# 05_LMS1_Misc.net
KiCad netlist of a schematic drawn in Altium Designer
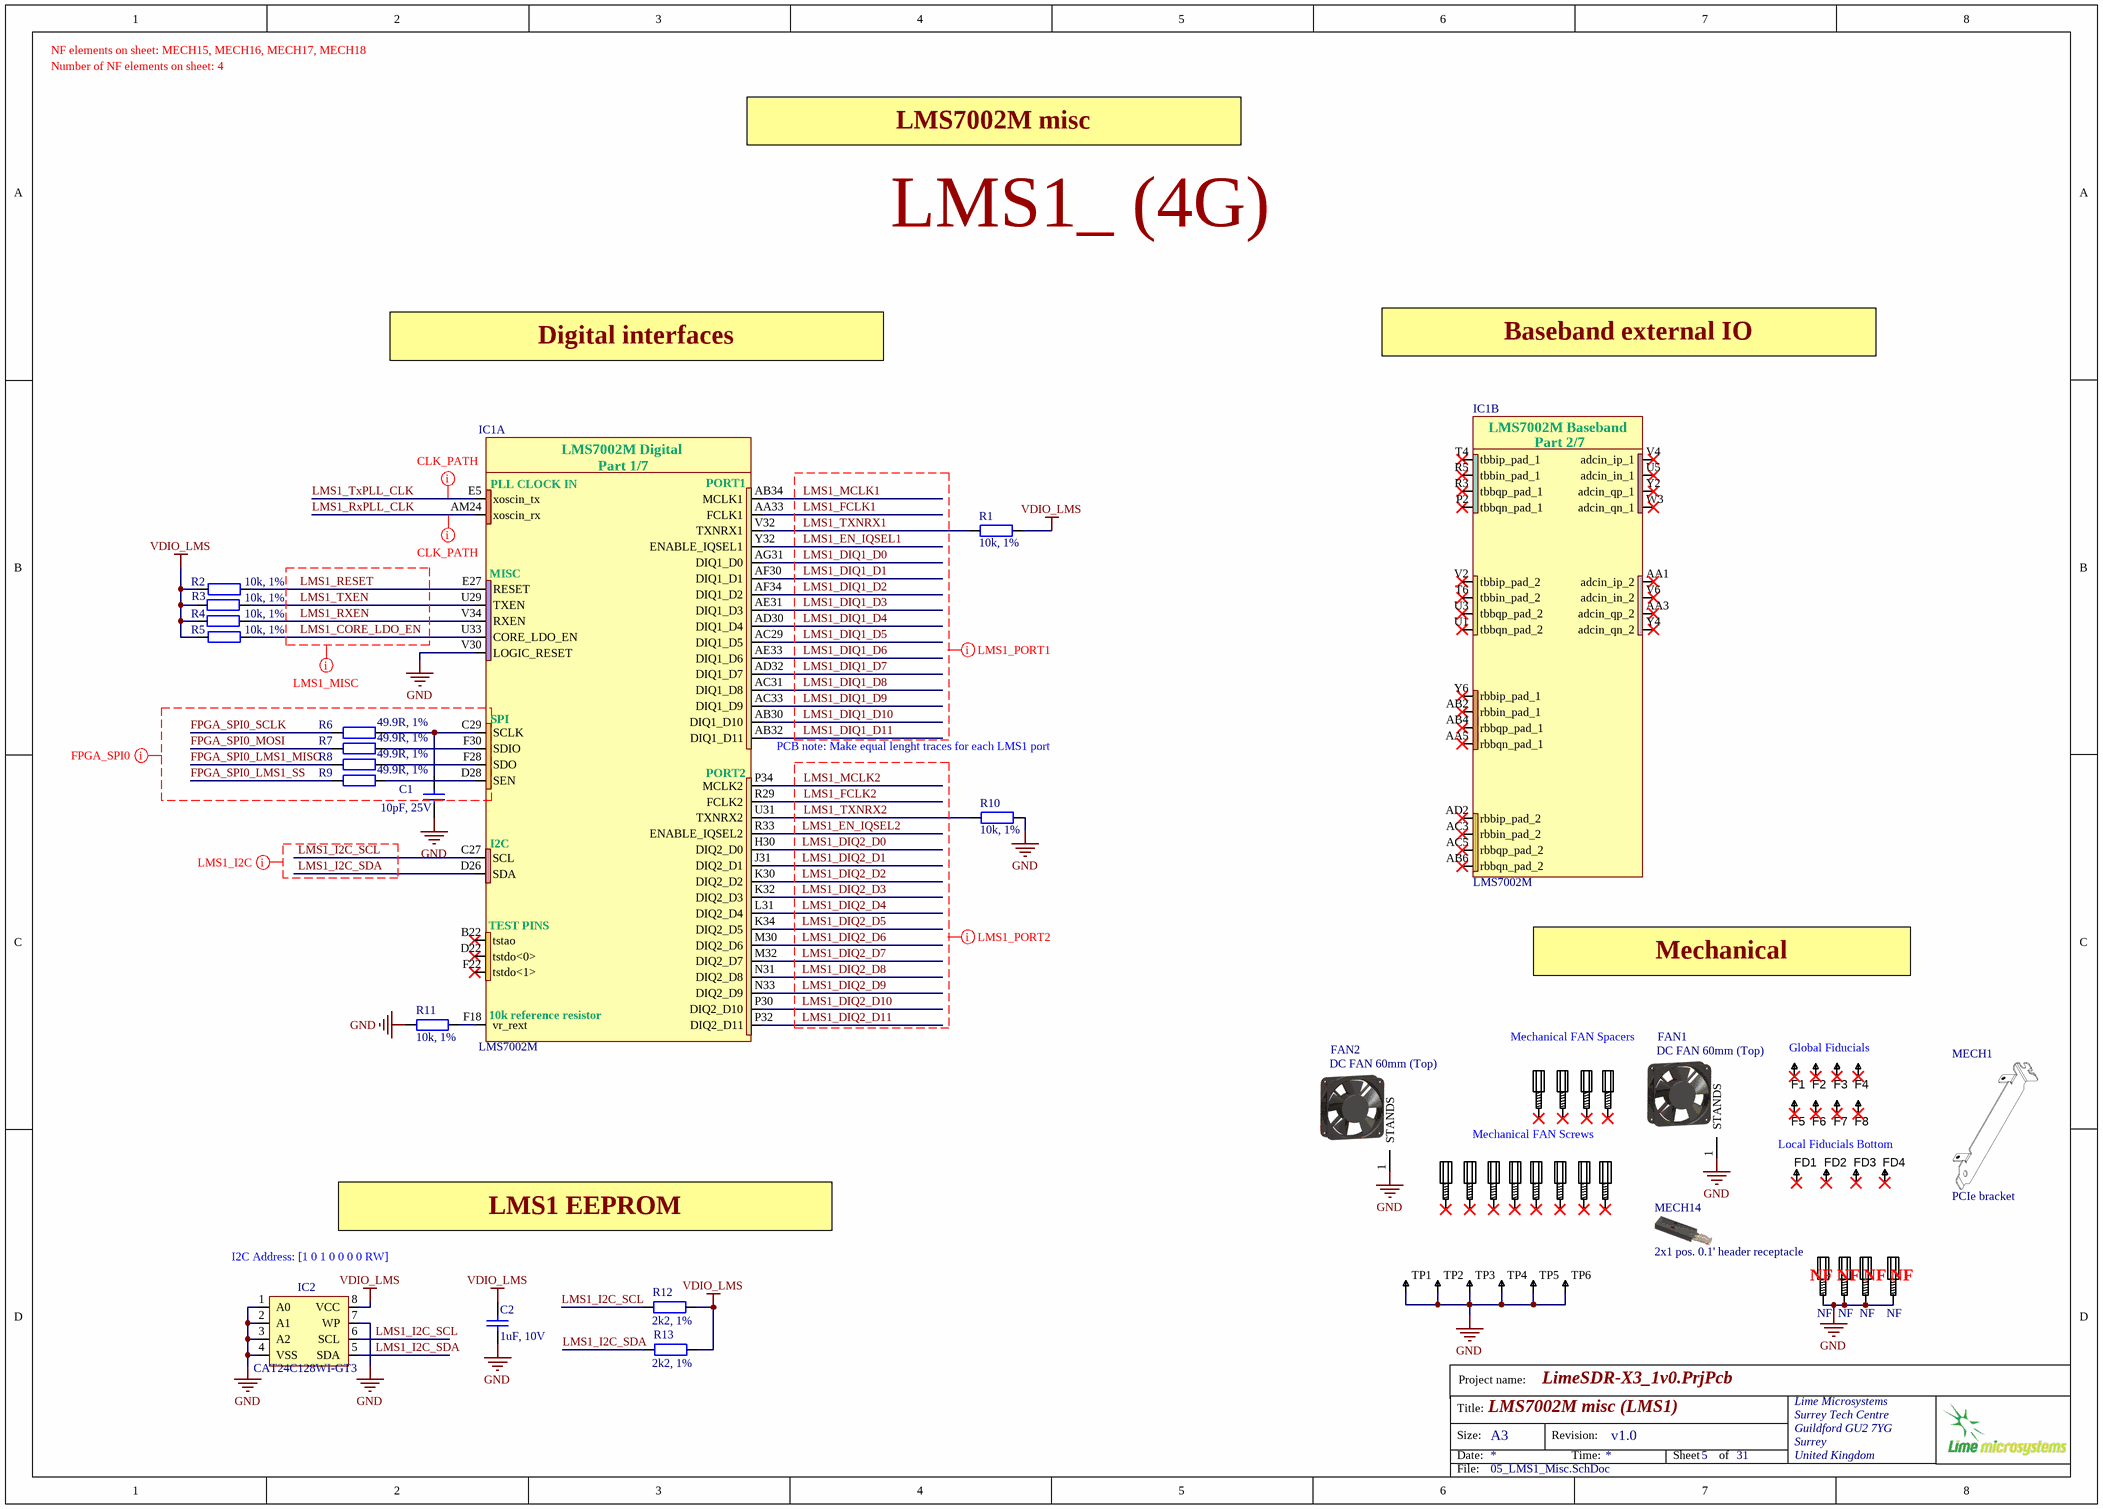
[diagram p0: 05_LMS1_Misc.SchDoc]

(export (version "E")
  (design (tool "Eeschema 10.0.6"))
  (components
    (comp (ref "C1")
      (value "10pF, 25V")
      (footprint "CAP0402")
      (fields (field (name "MANUFACTURER") "AVX"))
      (libsource (lib "") (part "Cap_0402_1"))
    )
    (comp (ref "C2")
      (value "1uF, 10V")
      (footprint "CAP0402")
      (fields (field (name "MANUFACTURER") "TDK"))
      (libsource (lib "LimeMicroAltiumLib_schLib") (part "Cap_0402"))
    )
    (comp (ref "F1")
      (value "Fiducial")
      (footprint "Fiducial")
      (libsource (lib "VGTU_Altium_lib") (part "Fiducial"))
    )
    (comp (ref "F2")
      (value "Fiducial")
      (footprint "Fiducial")
      (libsource (lib "VGTU_Altium_lib") (part "Fiducial"))
    )
    (comp (ref "F3")
      (value "Fiducial")
      (footprint "Fiducial")
      (libsource (lib "VGTU_Altium_lib") (part "Fiducial"))
    )
    (comp (ref "F4")
      (value "Fiducial")
      (footprint "Fiducial")
      (libsource (lib "VGTU_Altium_lib") (part "Fiducial"))
    )
    (comp (ref "F5")
      (value "Fiducial")
      (footprint "Fiducial")
      (libsource (lib "VGTU_Altium_lib") (part "Fiducial"))
    )
    (comp (ref "F6")
      (value "Fiducial")
      (footprint "Fiducial")
      (libsource (lib "VGTU_Altium_lib") (part "Fiducial"))
    )
    (comp (ref "F7")
      (value "Fiducial")
      (footprint "Fiducial")
      (libsource (lib "VGTU_Altium_lib") (part "Fiducial"))
    )
    (comp (ref "F8")
      (value "Fiducial")
      (footprint "Fiducial")
      (libsource (lib "VGTU_Altium_lib") (part "Fiducial"))
    )
    (comp (ref "FAN1")
      (value "DC FAN 60mm (Top)")
      (footprint "FAN_60mm")
      (fields (field (name "MANUFACTURER") "Sunon"))
      (libsource (lib "LimeMicroAltiumLib_schLib") (part "12V_DC_FAN"))
    )
    (comp (ref "FAN2")
      (value "DC FAN 60mm (Top)")
      (footprint "FAN_60mm")
      (fields (field (name "MANUFACTURER") "Sunon"))
      (libsource (lib "LimeMicroAltiumLib_schLib") (part "12V_DC_FAN"))
    )
    (comp (ref "FD1")
      (value "Fiducial")
      (footprint "Fiducial_local")
      (libsource (lib "LimeMicroAltiumLib_schLib") (part "Fiducial"))
    )
    (comp (ref "FD2")
      (value "Fiducial")
      (footprint "Fiducial_local")
      (libsource (lib "") (part "Fiducial_1"))
    )
    (comp (ref "FD3")
      (value "Fiducial")
      (footprint "Fiducial_local")
      (libsource (lib "") (part "Fiducial_2"))
    )
    (comp (ref "FD4")
      (value "Fiducial")
      (footprint "Fiducial_local")
      (libsource (lib "") (part "Fiducial_1"))
    )
    (comp (ref "IC1")
      (value "LMS7002M")
      (footprint "LMS7002M_v5")
      (description "Schematic symbol revision 4. Default footprint - 0.31mm pad")
      (fields (field (name "MANUFACTURER") "Lime Microsystems"))
      (libsource (lib "LimeMicroAltiumLib_schLib_r04") (part "LMS7002Mr4"))
    )
    (comp (ref "IC2")
      (value "CAT24C128WI-GT3")
      (footprint "SOIC127P600-8DL_v2")
      (fields (field (name "MANUFACTURER") "ON Semiconductor") (field (name "BASE PART NUMBER") "CAT24C128"))
      (libsource (lib "LimeMicroAltiumLib_schLib") (part "24FC64F"))
    )
    (comp (ref "MECH1")
      (value "PCIe bracket")
      (footprint "PCIe_bracket")
      (fields (field (name "MANUFACTURER") "Keystone Electronics"))
      (libsource (lib "LimeMicroAltiumLib_schLib_r01") (part "PCIe_bracket"))
    )
    (comp (ref "MECH2")
      (value "Spacer M3")
      (description "STANDOFF M/F MET 5MM HEX 10MM L")
      (fields (field (name "MANUFACTURER") "BOSSARD"))
      (libsource (lib "LimeMicroAltiumLib_schLib") (part "STANDOFF_M-F_THREADED_M3x8x10mm_HEX_5mm dia"))
    )
    (comp (ref "MECH3")
      (value "Spacer M3")
      (description "STANDOFF M/F MET 5MM HEX 10MM L")
      (fields (field (name "MANUFACTURER") "BOSSARD"))
      (libsource (lib "LimeMicroAltiumLib_schLib") (part "STANDOFF_M-F_THREADED_M3x8x10mm_HEX_5mm dia"))
    )
    (comp (ref "MECH4")
      (value "Spacer M3")
      (description "STANDOFF M/F MET 5MM HEX 10MM L")
      (fields (field (name "MANUFACTURER") "BOSSARD"))
      (libsource (lib "LimeMicroAltiumLib_schLib") (part "STANDOFF_M-F_THREADED_M3x8x10mm_HEX_5mm dia"))
    )
    (comp (ref "MECH5")
      (value "Spacer M3")
      (description "STANDOFF M/F MET 5MM HEX 10MM L")
      (fields (field (name "MANUFACTURER") "BOSSARD"))
      (libsource (lib "LimeMicroAltiumLib_schLib") (part "STANDOFF_M-F_THREADED_M3x8x10mm_HEX_5mm dia"))
    )
    (comp (ref "MECH6")
      (value "Screws M3")
      (description "STANDOFF M/F MET 5MM HEX 10MM L")
      (fields (field (name "MANUFACTURER") "BOSSARD"))
      (libsource (lib "") (part "STANDOFF_M-F_THREADED_M3x8x10mm_HEX_5mm dia_1"))
    )
    (comp (ref "MECH7")
      (value "Screws M3")
      (description "STANDOFF M/F MET 5MM HEX 10MM L")
      (fields (field (name "MANUFACTURER") "BOSSARD"))
      (libsource (lib "") (part "STANDOFF_M-F_THREADED_M3x8x10mm_HEX_5mm dia_1"))
    )
    (comp (ref "MECH8")
      (value "Screws M3")
      (description "STANDOFF M/F MET 5MM HEX 10MM L")
      (fields (field (name "MANUFACTURER") "BOSSARD"))
      (libsource (lib "") (part "STANDOFF_M-F_THREADED_M3x8x10mm_HEX_5mm dia_1"))
    )
    (comp (ref "MECH9")
      (value "Screws M3")
      (description "STANDOFF M/F MET 5MM HEX 10MM L")
      (fields (field (name "MANUFACTURER") "BOSSARD"))
      (libsource (lib "") (part "STANDOFF_M-F_THREADED_M3x8x10mm_HEX_5mm dia_1"))
    )
    (comp (ref "MECH10")
      (value "Screws M3")
      (description "STANDOFF M/F MET 5MM HEX 10MM L")
      (fields (field (name "MANUFACTURER") "BOSSARD"))
      (libsource (lib "") (part "STANDOFF_M-F_THREADED_M3x8x10mm_HEX_5mm dia_1"))
    )
    (comp (ref "MECH11")
      (value "Screws M3")
      (description "STANDOFF M/F MET 5MM HEX 10MM L")
      (fields (field (name "MANUFACTURER") "BOSSARD"))
      (libsource (lib "") (part "STANDOFF_M-F_THREADED_M3x8x10mm_HEX_5mm dia_1"))
    )
    (comp (ref "MECH12")
      (value "Screws M3")
      (description "STANDOFF M/F MET 5MM HEX 10MM L")
      (fields (field (name "MANUFACTURER") "BOSSARD"))
      (libsource (lib "") (part "STANDOFF_M-F_THREADED_M3x8x10mm_HEX_5mm dia_1"))
    )
    (comp (ref "MECH13")
      (value "Screws M3")
      (description "STANDOFF M/F MET 5MM HEX 10MM L")
      (fields (field (name "MANUFACTURER") "BOSSARD"))
      (libsource (lib "") (part "STANDOFF_M-F_THREADED_M3x8x10mm_HEX_5mm dia_1"))
    )
    (comp (ref "MECH14")
      (value "2x1 pos. 0.1' header receptacle")
      (fields (field (name "MANUFACTURER") "Molex"))
      (libsource (lib "LimeMicroAltiumLib_schLib_r01") (part "Header_1x2_receptacle"))
    )
    (comp (ref "MECH15")
      (value "Standoff")
      (footprint "PCB_standoff")
      (description "STANDOFF M/F MET 5MM HEX 10MM L")
      (fields (field (name "MANUFACTURER") "FIX&FASTEN") (field (name "ASSEMBLY INFO") "NF"))
      (libsource (lib "") (part "STANDOFF_M-F_THREADED_M3x8x10mm_HEX_5mm dia_1"))
    )
    (comp (ref "MECH16")
      (value "Standoff")
      (footprint "PCB_standoff")
      (description "STANDOFF M/F MET 5MM HEX 10MM L")
      (fields (field (name "MANUFACTURER") "FIX&FASTEN") (field (name "ASSEMBLY INFO") "NF"))
      (libsource (lib "") (part "STANDOFF_M-F_THREADED_M3x8x10mm_HEX_5mm dia_1"))
    )
    (comp (ref "MECH17")
      (value "Standoff")
      (footprint "PCB_standoff")
      (description "STANDOFF M/F MET 5MM HEX 10MM L")
      (fields (field (name "MANUFACTURER") "FIX&FASTEN") (field (name "ASSEMBLY INFO") "NF"))
      (libsource (lib "") (part "STANDOFF_M-F_THREADED_M3x8x10mm_HEX_5mm dia_1"))
    )
    (comp (ref "MECH18")
      (value "Standoff")
      (footprint "PCB_standoff")
      (description "STANDOFF M/F MET 5MM HEX 10MM L")
      (fields (field (name "MANUFACTURER") "FIX&FASTEN") (field (name "ASSEMBLY INFO") "NF"))
      (libsource (lib "") (part "STANDOFF_M-F_THREADED_M3x8x10mm_HEX_5mm dia_2"))
    )
    (comp (ref "R1")
      (value "10k, 1%")
      (footprint "RES0402")
      (fields (field (name "MANUFACTURER") "Yageo") (field (name "TOLERANCE") "±1%"))
      (libsource (lib "LimeMicroAltiumLib_schLib") (part "Res_0402"))
    )
    (comp (ref "R2")
      (value "10k, 1%")
      (footprint "RES0402")
      (fields (field (name "MANUFACTURER") "Yageo") (field (name "TOLERANCE") "±1%"))
      (libsource (lib "LimeMicroAltiumLib_schLib") (part "Res_0402"))
    )
    (comp (ref "R3")
      (value "10k, 1%")
      (footprint "RES0402")
      (fields (field (name "MANUFACTURER") "Yageo") (field (name "TOLERANCE") "±1%"))
      (libsource (lib "LimeMicroAltiumLib_schLib") (part "Res_0402"))
    )
    (comp (ref "R4")
      (value "10k, 1%")
      (footprint "RES0402")
      (fields (field (name "MANUFACTURER") "Yageo") (field (name "TOLERANCE") "±1%"))
      (libsource (lib "LimeMicroAltiumLib_schLib") (part "Res_0402"))
    )
    (comp (ref "R5")
      (value "10k, 1%")
      (footprint "RES0402")
      (fields (field (name "MANUFACTURER") "Yageo") (field (name "TOLERANCE") "±1%"))
      (libsource (lib "LimeMicroAltiumLib_schLib") (part "Res_0402"))
    )
    (comp (ref "R6")
      (value "49.9R, 1%")
      (footprint "RES0402")
      (fields
        (field (name "TOLERANCE") "±1%")
        (field (name "MANUFACTURER") "Samsung Electro-Mechanics America, Inc.")
        (field (name "MANUFACTURER PART NUMBER") "RC1005F49R9CS")
      )
      (libsource (lib "LimeMicroAltiumLib_schLib") (part "Res_0402"))
    )
    (comp (ref "R7")
      (value "49.9R, 1%")
      (footprint "RES0402")
      (fields
        (field (name "TOLERANCE") "±1%")
        (field (name "MANUFACTURER") "Samsung Electro-Mechanics America, Inc.")
        (field (name "MANUFACTURER PART NUMBER") "RC1005F49R9CS")
      )
      (libsource (lib "LimeMicroAltiumLib_schLib") (part "Res_0402"))
    )
    (comp (ref "R8")
      (value "49.9R, 1%")
      (footprint "RES0402")
      (fields
        (field (name "TOLERANCE") "±1%")
        (field (name "MANUFACTURER") "Samsung Electro-Mechanics America, Inc.")
        (field (name "MANUFACTURER PART NUMBER") "RC1005F49R9CS")
      )
      (libsource (lib "LimeMicroAltiumLib_schLib") (part "Res_0402"))
    )
    (comp (ref "R9")
      (value "49.9R, 1%")
      (footprint "RES0402")
      (fields
        (field (name "TOLERANCE") "±1%")
        (field (name "MANUFACTURER") "Samsung Electro-Mechanics America, Inc.")
        (field (name "MANUFACTURER PART NUMBER") "RC1005F49R9CS")
      )
      (libsource (lib "LimeMicroAltiumLib_schLib") (part "Res_0402"))
    )
    (comp (ref "R10")
      (value "10k, 1%")
      (footprint "RES0402")
      (fields (field (name "MANUFACTURER") "Yageo") (field (name "TOLERANCE") "±1%"))
      (libsource (lib "LimeMicroAltiumLib_schLib") (part "Res_0402"))
    )
    (comp (ref "R11")
      (value "10k, 1%")
      (footprint "RES0402")
      (fields (field (name "MANUFACTURER") "Yageo") (field (name "TOLERANCE") "±1%"))
      (libsource (lib "") (part "Res_0402_1"))
    )
    (comp (ref "R12")
      (value "2k2, 1%")
      (footprint "RES0402")
      (fields (field (name "MANUFACTURER") "Stackpole Electronics Inc") (field (name "TOLERANCE") "±1%"))
      (libsource (lib "LimeMicroAltiumLib_schLib") (part "Res_0402"))
    )
    (comp (ref "R13")
      (value "2k2, 1%")
      (footprint "RES0402")
      (fields (field (name "MANUFACTURER") "Stackpole Electronics Inc") (field (name "TOLERANCE") "±1%"))
      (libsource (lib "LimeMicroAltiumLib_schLib") (part "Res_0402"))
    )
    (comp (ref "TP1")
      (value "TESTPOINT_THT_MINI")
      (footprint "TP-SMD-LOW_PROFILE")
      (description "Test Point PCB mount Miniature White")
      (fields (field (name "MANUFACTURER") "Harwin Inc"))
      (libsource (lib "LimeMicroAltiumLib_schLib") (part "TESTPOINT_THT_MINI"))
    )
    (comp (ref "TP2")
      (value "TESTPOINT_THT_MINI")
      (footprint "TP-SMD-LOW_PROFILE")
      (description "Test Point PCB mount Miniature White")
      (fields (field (name "MANUFACTURER") "Harwin Inc"))
      (libsource (lib "LimeMicroAltiumLib_schLib") (part "TESTPOINT_THT_MINI"))
    )
    (comp (ref "TP3")
      (value "TESTPOINT_THT_MINI")
      (footprint "TP-SMD-LOW_PROFILE")
      (description "Test Point PCB mount Miniature White")
      (fields (field (name "MANUFACTURER") "Harwin Inc"))
      (libsource (lib "LimeMicroAltiumLib_schLib") (part "TESTPOINT_THT_MINI"))
    )
    (comp (ref "TP4")
      (value "TESTPOINT_THT_MINI")
      (footprint "TP-SMD-LOW_PROFILE")
      (description "Test Point PCB mount Miniature White")
      (fields (field (name "MANUFACTURER") "Harwin Inc"))
      (libsource (lib "LimeMicroAltiumLib_schLib") (part "TESTPOINT_THT_MINI"))
    )
    (comp (ref "TP5")
      (value "TESTPOINT_THT_MINI")
      (footprint "TP-SMD-LOW_PROFILE")
      (description "Test Point PCB mount Miniature White")
      (fields (field (name "MANUFACTURER") "Harwin Inc"))
      (libsource (lib "LimeMicroAltiumLib_schLib") (part "TESTPOINT_THT_MINI"))
    )
    (comp (ref "TP6")
      (value "TESTPOINT_THT_MINI")
      (footprint "TP-SMD-LOW_PROFILE")
      (description "Test Point PCB mount Miniature White")
      (fields (field (name "MANUFACTURER") "Harwin Inc"))
      (libsource (lib "LimeMicroAltiumLib_schLib") (part "TESTPOINT_THT_MINI"))
    )
  )
  (nets
    (net (code "1") (name "/FPGA_SPI0_LMS1_MISO") (class "Default")
      (node (ref "R8") (pin "2") (pinfunction "2_2") (pintype "passive"))
    )
    (net (code "2") (name "/FPGA_SPI0_LMS1_SS") (class "Default")
      (node (ref "R9") (pin "2") (pinfunction "2_2") (pintype "passive"))
    )
    (net (code "3") (name "/FPGA_SPI0_MOSI") (class "Default")
      (node (ref "R7") (pin "2") (pinfunction "2_2") (pintype "passive"))
    )
    (net (code "4") (name "/FPGA_SPI0_SCLK") (class "Default")
      (node (ref "R6") (pin "2") (pinfunction "2_2") (pintype "passive"))
    )
    (net (code "5") (name "/LMS1_CORE_LDO_EN") (class "Default")
      (node (ref "IC1") (pin "U33") (pinfunction "CORE_LDO_EN_U33") (pintype "passive"))
      (node (ref "R5") (pin "1") (pinfunction "1_1") (pintype "passive"))
    )
    (net (code "6") (name "/LMS1_DIQ1_D0") (class "Default")
      (node (ref "IC1") (pin "AG31") (pinfunction "DIQ1_D0_AG31") (pintype "passive"))
    )
    (net (code "7") (name "/LMS1_DIQ1_D1") (class "Default")
      (node (ref "IC1") (pin "AF30") (pinfunction "DIQ1_D1_AF30") (pintype "passive"))
    )
    (net (code "8") (name "/LMS1_DIQ1_D2") (class "Default")
      (node (ref "IC1") (pin "AF34") (pinfunction "DIQ1_D2_AF34") (pintype "passive"))
    )
    (net (code "9") (name "/LMS1_DIQ1_D3") (class "Default")
      (node (ref "IC1") (pin "AE31") (pinfunction "DIQ1_D3_AE31") (pintype "passive"))
    )
    (net (code "10") (name "/LMS1_DIQ1_D4") (class "Default")
      (node (ref "IC1") (pin "AD30") (pinfunction "DIQ1_D4_AD30") (pintype "passive"))
    )
    (net (code "11") (name "/LMS1_DIQ1_D5") (class "Default")
      (node (ref "IC1") (pin "AC29") (pinfunction "DIQ1_D5_AC29") (pintype "passive"))
    )
    (net (code "12") (name "/LMS1_DIQ1_D6") (class "Default")
      (node (ref "IC1") (pin "AE33") (pinfunction "DIQ1_D6_AE33") (pintype "passive"))
    )
    (net (code "13") (name "/LMS1_DIQ1_D7") (class "Default")
      (node (ref "IC1") (pin "AD32") (pinfunction "DIQ1_D7_AD32") (pintype "passive"))
    )
    (net (code "14") (name "/LMS1_DIQ1_D8") (class "Default")
      (node (ref "IC1") (pin "AC31") (pinfunction "DIQ1_D8_AC31") (pintype "passive"))
    )
    (net (code "15") (name "/LMS1_DIQ1_D9") (class "Default")
      (node (ref "IC1") (pin "AC33") (pinfunction "DIQ1_D9_AC33") (pintype "passive"))
    )
    (net (code "16") (name "/LMS1_DIQ1_D10") (class "Default")
      (node (ref "IC1") (pin "AB30") (pinfunction "DIQ1_D10_AB30") (pintype "passive"))
    )
    (net (code "17") (name "/LMS1_DIQ1_D11") (class "Default")
      (node (ref "IC1") (pin "AB32") (pinfunction "DIQ1_D11_AB32") (pintype "passive"))
    )
    (net (code "18") (name "/LMS1_DIQ2_D0") (class "Default")
      (node (ref "IC1") (pin "H30") (pinfunction "DIQ2_D0_H30") (pintype "passive"))
    )
    (net (code "19") (name "/LMS1_DIQ2_D1") (class "Default")
      (node (ref "IC1") (pin "J31") (pinfunction "DIQ2_D1_J31") (pintype "passive"))
    )
    (net (code "20") (name "/LMS1_DIQ2_D2") (class "Default")
      (node (ref "IC1") (pin "K30") (pinfunction "DIQ2_D2_K30") (pintype "passive"))
    )
    (net (code "21") (name "/LMS1_DIQ2_D3") (class "Default")
      (node (ref "IC1") (pin "K32") (pinfunction "DIQ2_D3_K32") (pintype "passive"))
    )
    (net (code "22") (name "/LMS1_DIQ2_D4") (class "Default")
      (node (ref "IC1") (pin "L31") (pinfunction "DIQ2_D4_L31") (pintype "passive"))
    )
    (net (code "23") (name "/LMS1_DIQ2_D5") (class "Default")
      (node (ref "IC1") (pin "K34") (pinfunction "DIQ2_D5_K34") (pintype "passive"))
    )
    (net (code "24") (name "/LMS1_DIQ2_D6") (class "Default")
      (node (ref "IC1") (pin "M30") (pinfunction "DIQ2_D6_M30") (pintype "passive"))
    )
    (net (code "25") (name "/LMS1_DIQ2_D7") (class "Default")
      (node (ref "IC1") (pin "M32") (pinfunction "DIQ2_D7_M32") (pintype "passive"))
    )
    (net (code "26") (name "/LMS1_DIQ2_D8") (class "Default")
      (node (ref "IC1") (pin "N31") (pinfunction "DIQ2_D8_N31") (pintype "passive"))
    )
    (net (code "27") (name "/LMS1_DIQ2_D9") (class "Default")
      (node (ref "IC1") (pin "N33") (pinfunction "DIQ2_D9_N33") (pintype "passive"))
    )
    (net (code "28") (name "/LMS1_DIQ2_D10") (class "Default")
      (node (ref "IC1") (pin "P30") (pinfunction "DIQ2_D10_P30") (pintype "passive"))
    )
    (net (code "29") (name "/LMS1_DIQ2_D11") (class "Default")
      (node (ref "IC1") (pin "P32") (pinfunction "DIQ2_D11_P32") (pintype "passive"))
    )
    (net (code "30") (name "/LMS1_EN_IQSEL1") (class "Default")
      (node (ref "IC1") (pin "Y32") (pinfunction "ENABLE_IQSEL1_Y32") (pintype "passive"))
    )
    (net (code "31") (name "/LMS1_EN_IQSEL2") (class "Default")
      (node (ref "IC1") (pin "R33") (pinfunction "ENABLE_IQSEL2_R33") (pintype "passive"))
    )
    (net (code "32") (name "/LMS1_FCLK1") (class "Default")
      (node (ref "IC1") (pin "AA33") (pinfunction "FCLK1_AA33") (pintype "passive"))
    )
    (net (code "33") (name "/LMS1_FCLK2") (class "Default")
      (node (ref "IC1") (pin "R29") (pinfunction "FCLK2_R29") (pintype "passive"))
    )
    (net (code "34") (name "/LMS1_I2C_SCL") (class "Default")
      (node (ref "IC1") (pin "C27") (pinfunction "SCL_C27") (pintype "passive"))
      (node (ref "IC2") (pin "6") (pinfunction "SCL_6") (pintype "passive"))
      (node (ref "R12") (pin "2") (pinfunction "2_2") (pintype "passive"))
    )
    (net (code "35") (name "/LMS1_I2C_SDA") (class "Default")
      (node (ref "IC1") (pin "D26") (pinfunction "SDA_D26") (pintype "passive"))
      (node (ref "IC2") (pin "5") (pinfunction "SDA_5") (pintype "passive"))
      (node (ref "R13") (pin "2") (pinfunction "2_2") (pintype "passive"))
    )
    (net (code "36") (name "/LMS1_MCLK1") (class "Default")
      (node (ref "IC1") (pin "AB34") (pinfunction "MCLK1_AB34") (pintype "passive"))
    )
    (net (code "37") (name "/LMS1_MCLK2") (class "Default")
      (node (ref "IC1") (pin "P34") (pinfunction "MCLK2_P34") (pintype "passive"))
    )
    (net (code "38") (name "/LMS1_RESET") (class "Default")
      (node (ref "IC1") (pin "E27") (pinfunction "RESET_E27") (pintype "passive"))
      (node (ref "R2") (pin "1") (pinfunction "1_1") (pintype "passive"))
    )
    (net (code "39") (name "/LMS1_RXEN") (class "Default")
      (node (ref "IC1") (pin "V34") (pinfunction "RXEN_V34") (pintype "passive"))
      (node (ref "R4") (pin "2") (pinfunction "2_2") (pintype "passive"))
    )
    (net (code "40") (name "/LMS1_RxPLL_CLK") (class "Default")
      (node (ref "IC1") (pin "AM24") (pinfunction "xoscin_rx_AM24") (pintype "passive"))
    )
    (net (code "41") (name "/LMS1_TXEN") (class "Default")
      (node (ref "IC1") (pin "U29") (pinfunction "TXEN_U29") (pintype "passive"))
      (node (ref "R3") (pin "2") (pinfunction "2_2") (pintype "passive"))
    )
    (net (code "42") (name "/LMS1_TXNRX1") (class "Default")
      (node (ref "IC1") (pin "V32") (pinfunction "TXNRX1_V32") (pintype "passive"))
      (node (ref "R1") (pin "1") (pinfunction "1_1") (pintype "passive"))
    )
    (net (code "43") (name "/LMS1_TXNRX2") (class "Default")
      (node (ref "IC1") (pin "U31") (pinfunction "TXNRX2_U31") (pintype "passive"))
      (node (ref "R10") (pin "2") (pinfunction "2_2") (pintype "passive"))
    )
    (net (code "44") (name "/LMS1_TxPLL_CLK") (class "Default")
      (node (ref "IC1") (pin "E5") (pinfunction "xoscin_tx_E5") (pintype "passive"))
    )
    (net (code "45") (name "GND") (class "Default")
      (node (ref "C1") (pin "2") (pinfunction "2_2") (pintype "passive"))
      (node (ref "C2") (pin "2") (pinfunction "2_2") (pintype "passive"))
      (node (ref "FAN1") (pin "1") (pinfunction "STANDS_1") (pintype "passive"))
      (node (ref "FAN2") (pin "1") (pinfunction "STANDS_1") (pintype "passive"))
      (node (ref "IC1") (pin "V30") (pinfunction "LOGIC_RESET_V30") (pintype "passive"))
      (node (ref "IC2") (pin "1") (pinfunction "A0_1") (pintype "passive"))
      (node (ref "IC2") (pin "2") (pinfunction "A1_2") (pintype "passive"))
      (node (ref "IC2") (pin "3") (pinfunction "A2_3") (pintype "passive"))
      (node (ref "IC2") (pin "4") (pinfunction "VSS_4") (pintype "passive"))
      (node (ref "IC2") (pin "7") (pinfunction "WP_7") (pintype "passive"))
      (node (ref "MECH15") (pin "MH1") (pinfunction "MH1_MH1") (pintype "passive"))
      (node (ref "MECH16") (pin "MH1") (pinfunction "MH1_MH1") (pintype "passive"))
      (node (ref "MECH17") (pin "MH1") (pinfunction "MH1_MH1") (pintype "passive"))
      (node (ref "MECH18") (pin "MH1") (pinfunction "MH1_MH1") (pintype "passive"))
      (node (ref "R10") (pin "1") (pinfunction "1_1") (pintype "passive"))
      (node (ref "R11") (pin "2") (pinfunction "2_2") (pintype "passive"))
      (node (ref "TP1") (pin "1") (pintype "passive"))
      (node (ref "TP2") (pin "1") (pintype "passive"))
      (node (ref "TP3") (pin "1") (pintype "passive"))
      (node (ref "TP4") (pin "1") (pintype "passive"))
      (node (ref "TP5") (pin "1") (pintype "passive"))
      (node (ref "TP6") (pin "1") (pintype "passive"))
    )
    (net (code "46") (name "Net-(IC1A-SCLK)") (class "Default")
      (node (ref "C1") (pin "1") (pinfunction "1_1") (pintype "passive"))
      (node (ref "IC1") (pin "C29") (pinfunction "SCLK_C29") (pintype "passive"))
      (node (ref "R6") (pin "1") (pinfunction "1_1") (pintype "passive"))
    )
    (net (code "47") (name "Net-(IC1A-SDIO)") (class "Default")
      (node (ref "IC1") (pin "F30") (pinfunction "SDIO_F30") (pintype "passive"))
      (node (ref "R7") (pin "1") (pinfunction "1_1") (pintype "passive"))
    )
    (net (code "48") (name "Net-(IC1A-SDO)") (class "Default")
      (node (ref "IC1") (pin "F28") (pinfunction "SDO_F28") (pintype "passive"))
      (node (ref "R8") (pin "1") (pinfunction "1_1") (pintype "passive"))
    )
    (net (code "49") (name "Net-(IC1A-SEN)") (class "Default")
      (node (ref "IC1") (pin "D28") (pinfunction "SEN_D28") (pintype "passive"))
      (node (ref "R9") (pin "1") (pinfunction "1_1") (pintype "passive"))
    )
    (net (code "50") (name "Net-(IC1A-vr_rext)") (class "Default")
      (node (ref "IC1") (pin "F18") (pinfunction "vr_rext_F18") (pintype "passive"))
      (node (ref "R11") (pin "1") (pinfunction "1_1") (pintype "passive"))
    )
    (net (code "51") (name "VDIO_LMS") (class "Default")
      (node (ref "C2") (pin "1") (pinfunction "1_1") (pintype "passive"))
      (node (ref "IC2") (pin "8") (pinfunction "VCC_8") (pintype "passive"))
      (node (ref "R1") (pin "2") (pinfunction "2_2") (pintype "passive"))
      (node (ref "R12") (pin "1") (pinfunction "1_1") (pintype "passive"))
      (node (ref "R13") (pin "1") (pinfunction "1_1") (pintype "passive"))
      (node (ref "R2") (pin "2") (pinfunction "2_2") (pintype "passive"))
      (node (ref "R3") (pin "1") (pinfunction "1_1") (pintype "passive"))
      (node (ref "R4") (pin "1") (pinfunction "1_1") (pintype "passive"))
      (node (ref "R5") (pin "2") (pinfunction "2_2") (pintype "passive"))
    )
    (net (code "52") (name "unconnected-(F1-Pad1)") (class "Default")
      (node (ref "F1") (pin "1") (pintype "passive+no_connect"))
    )
    (net (code "53") (name "unconnected-(F2-Pad1)") (class "Default")
      (node (ref "F2") (pin "1") (pintype "passive+no_connect"))
    )
    (net (code "54") (name "unconnected-(F3-Pad1)") (class "Default")
      (node (ref "F3") (pin "1") (pintype "passive+no_connect"))
    )
    (net (code "55") (name "unconnected-(F4-Pad1)") (class "Default")
      (node (ref "F4") (pin "1") (pintype "passive+no_connect"))
    )
    (net (code "56") (name "unconnected-(F5-Pad1)") (class "Default")
      (node (ref "F5") (pin "1") (pintype "passive+no_connect"))
    )
    (net (code "57") (name "unconnected-(F6-Pad1)") (class "Default")
      (node (ref "F6") (pin "1") (pintype "passive+no_connect"))
    )
    (net (code "58") (name "unconnected-(F7-Pad1)") (class "Default")
      (node (ref "F7") (pin "1") (pintype "passive+no_connect"))
    )
    (net (code "59") (name "unconnected-(F8-Pad1)") (class "Default")
      (node (ref "F8") (pin "1") (pintype "passive+no_connect"))
    )
    (net (code "60") (name "unconnected-(FD1-Pad1)") (class "Default")
      (node (ref "FD1") (pin "1") (pintype "passive+no_connect"))
    )
    (net (code "61") (name "unconnected-(FD2-Pad1)") (class "Default")
      (node (ref "FD2") (pin "1") (pintype "passive+no_connect"))
    )
    (net (code "62") (name "unconnected-(FD3-Pad1)") (class "Default")
      (node (ref "FD3") (pin "1") (pintype "passive+no_connect"))
    )
    (net (code "63") (name "unconnected-(FD4-Pad1)") (class "Default")
      (node (ref "FD4") (pin "1") (pintype "passive+no_connect"))
    )
    (net (code "64") (name "unconnected-(IC1A-tstao-PadB22)") (class "Default")
      (node (ref "IC1") (pin "B22") (pinfunction "tstao_B22") (pintype "passive"))
    )
    (net (code "65") (name "unconnected-(IC1A-tstdo<0>-PadD22)") (class "Default")
      (node (ref "IC1") (pin "D22") (pinfunction "tstdo<0>_D22") (pintype "passive"))
    )
    (net (code "66") (name "unconnected-(IC1A-tstdo<1>-PadF22)") (class "Default")
      (node (ref "IC1") (pin "F22") (pinfunction "tstdo<1>_F22") (pintype "passive"))
    )
    (net (code "67") (name "unconnected-(IC1B-adcin_in_1-PadU5)") (class "Default")
      (node (ref "IC1") (pin "U5") (pinfunction "adcin_in_1_U5") (pintype "passive+no_connect"))
    )
    (net (code "68") (name "unconnected-(IC1B-adcin_in_2-PadV6)") (class "Default")
      (node (ref "IC1") (pin "V6") (pinfunction "adcin_in_2_V6") (pintype "passive+no_connect"))
    )
    (net (code "69") (name "unconnected-(IC1B-adcin_ip_1-PadV4)") (class "Default")
      (node (ref "IC1") (pin "V4") (pinfunction "adcin_ip_1_V4") (pintype "passive+no_connect"))
    )
    (net (code "70") (name "unconnected-(IC1B-adcin_ip_2-PadAA1)") (class "Default")
      (node (ref "IC1") (pin "AA1") (pinfunction "adcin_ip_2_AA1") (pintype "passive+no_connect"))
    )
    (net (code "71") (name "unconnected-(IC1B-adcin_qn_1-PadW3)") (class "Default")
      (node (ref "IC1") (pin "W3") (pinfunction "adcin_qn_1_W3") (pintype "passive+no_connect"))
    )
    (net (code "72") (name "unconnected-(IC1B-adcin_qn_2-PadY4)") (class "Default")
      (node (ref "IC1") (pin "Y4") (pinfunction "adcin_qn_2_Y4") (pintype "passive+no_connect"))
    )
    (net (code "73") (name "unconnected-(IC1B-adcin_qp_1-PadY2)") (class "Default")
      (node (ref "IC1") (pin "Y2") (pinfunction "adcin_qp_1_Y2") (pintype "passive+no_connect"))
    )
    (net (code "74") (name "unconnected-(IC1B-adcin_qp_2-PadAA3)") (class "Default")
      (node (ref "IC1") (pin "AA3") (pinfunction "adcin_qp_2_AA3") (pintype "passive+no_connect"))
    )
    (net (code "75") (name "unconnected-(IC1B-rbbin_pad_1-PadAB2)") (class "Default")
      (node (ref "IC1") (pin "AB2") (pinfunction "rbbin_pad_1_AB2") (pintype "passive+no_connect"))
    )
    (net (code "76") (name "unconnected-(IC1B-rbbin_pad_2-PadAC3)") (class "Default")
      (node (ref "IC1") (pin "AC3") (pinfunction "rbbin_pad_2_AC3") (pintype "passive+no_connect"))
    )
    (net (code "77") (name "unconnected-(IC1B-rbbip_pad_1-PadY6)") (class "Default")
      (node (ref "IC1") (pin "Y6") (pinfunction "rbbip_pad_1_Y6") (pintype "passive+no_connect"))
    )
    (net (code "78") (name "unconnected-(IC1B-rbbip_pad_2-PadAD2)") (class "Default")
      (node (ref "IC1") (pin "AD2") (pinfunction "rbbip_pad_2_AD2") (pintype "passive+no_connect"))
    )
    (net (code "79") (name "unconnected-(IC1B-rbbqn_pad_1-PadAA5)") (class "Default")
      (node (ref "IC1") (pin "AA5") (pinfunction "rbbqn_pad_1_AA5") (pintype "passive+no_connect"))
    )
    (net (code "80") (name "unconnected-(IC1B-rbbqn_pad_2-PadAB6)") (class "Default")
      (node (ref "IC1") (pin "AB6") (pinfunction "rbbqn_pad_2_AB6") (pintype "passive+no_connect"))
    )
    (net (code "81") (name "unconnected-(IC1B-rbbqp_pad_1-PadAB4)") (class "Default")
      (node (ref "IC1") (pin "AB4") (pinfunction "rbbqp_pad_1_AB4") (pintype "passive+no_connect"))
    )
    (net (code "82") (name "unconnected-(IC1B-rbbqp_pad_2-PadAC5)") (class "Default")
      (node (ref "IC1") (pin "AC5") (pinfunction "rbbqp_pad_2_AC5") (pintype "passive+no_connect"))
    )
    (net (code "83") (name "unconnected-(IC1B-tbbin_pad_1-PadR5)") (class "Default")
      (node (ref "IC1") (pin "R5") (pinfunction "tbbin_pad_1_R5") (pintype "passive+no_connect"))
    )
    (net (code "84") (name "unconnected-(IC1B-tbbin_pad_2-PadT6)") (class "Default")
      (node (ref "IC1") (pin "T6") (pinfunction "tbbin_pad_2_T6") (pintype "passive+no_connect"))
    )
    (net (code "85") (name "unconnected-(IC1B-tbbip_pad_1-PadT4)") (class "Default")
      (node (ref "IC1") (pin "T4") (pinfunction "tbbip_pad_1_T4") (pintype "passive+no_connect"))
    )
    (net (code "86") (name "unconnected-(IC1B-tbbip_pad_2-PadV2)") (class "Default")
      (node (ref "IC1") (pin "V2") (pinfunction "tbbip_pad_2_V2") (pintype "passive+no_connect"))
    )
    (net (code "87") (name "unconnected-(IC1B-tbbqn_pad_1-PadP2)") (class "Default")
      (node (ref "IC1") (pin "P2") (pinfunction "tbbqn_pad_1_P2") (pintype "passive+no_connect"))
    )
    (net (code "88") (name "unconnected-(IC1B-tbbqn_pad_2-PadU1)") (class "Default")
      (node (ref "IC1") (pin "U1") (pinfunction "tbbqn_pad_2_U1") (pintype "passive+no_connect"))
    )
    (net (code "89") (name "unconnected-(IC1B-tbbqp_pad_1-PadR3)") (class "Default")
      (node (ref "IC1") (pin "R3") (pinfunction "tbbqp_pad_1_R3") (pintype "passive+no_connect"))
    )
    (net (code "90") (name "unconnected-(IC1B-tbbqp_pad_2-PadU3)") (class "Default")
      (node (ref "IC1") (pin "U3") (pinfunction "tbbqp_pad_2_U3") (pintype "passive+no_connect"))
    )
    (net (code "91") (name "unconnected-(MECH2-PadMH1)") (class "Default")
      (node (ref "MECH2") (pin "MH1") (pinfunction "MH1_MH1") (pintype "passive+no_connect"))
    )
    (net (code "92") (name "unconnected-(MECH3-PadMH1)") (class "Default")
      (node (ref "MECH3") (pin "MH1") (pinfunction "MH1_MH1") (pintype "passive+no_connect"))
    )
    (net (code "93") (name "unconnected-(MECH4-PadMH1)") (class "Default")
      (node (ref "MECH4") (pin "MH1") (pinfunction "MH1_MH1") (pintype "passive+no_connect"))
    )
    (net (code "94") (name "unconnected-(MECH5-PadMH1)") (class "Default")
      (node (ref "MECH5") (pin "MH1") (pinfunction "MH1_MH1") (pintype "passive+no_connect"))
    )
    (net (code "95") (name "unconnected-(MECH6-PadMH1)") (class "Default")
      (node (ref "MECH6") (pin "MH1") (pinfunction "MH1_MH1") (pintype "passive+no_connect"))
    )
    (net (code "96") (name "unconnected-(MECH7-PadMH1)") (class "Default")
      (node (ref "MECH7") (pin "MH1") (pinfunction "MH1_MH1") (pintype "passive+no_connect"))
    )
    (net (code "97") (name "unconnected-(MECH8-PadMH1)") (class "Default")
      (node (ref "MECH8") (pin "MH1") (pinfunction "MH1_MH1") (pintype "passive+no_connect"))
    )
    (net (code "98") (name "unconnected-(MECH9-PadMH1)") (class "Default")
      (node (ref "MECH9") (pin "MH1") (pinfunction "MH1_MH1") (pintype "passive+no_connect"))
    )
    (net (code "99") (name "unconnected-(MECH10-PadMH1)") (class "Default")
      (node (ref "MECH10") (pin "MH1") (pinfunction "MH1_MH1") (pintype "passive+no_connect"))
    )
    (net (code "100") (name "unconnected-(MECH11-PadMH1)") (class "Default")
      (node (ref "MECH11") (pin "MH1") (pinfunction "MH1_MH1") (pintype "passive+no_connect"))
    )
    (net (code "101") (name "unconnected-(MECH12-PadMH1)") (class "Default")
      (node (ref "MECH12") (pin "MH1") (pinfunction "MH1_MH1") (pintype "passive+no_connect"))
    )
    (net (code "102") (name "unconnected-(MECH13-PadMH1)") (class "Default")
      (node (ref "MECH13") (pin "MH1") (pinfunction "MH1_MH1") (pintype "passive+no_connect"))
    )
  )
)
